# electrode_tester.net
KiCad netlist of a schematic drawn in EAGLE
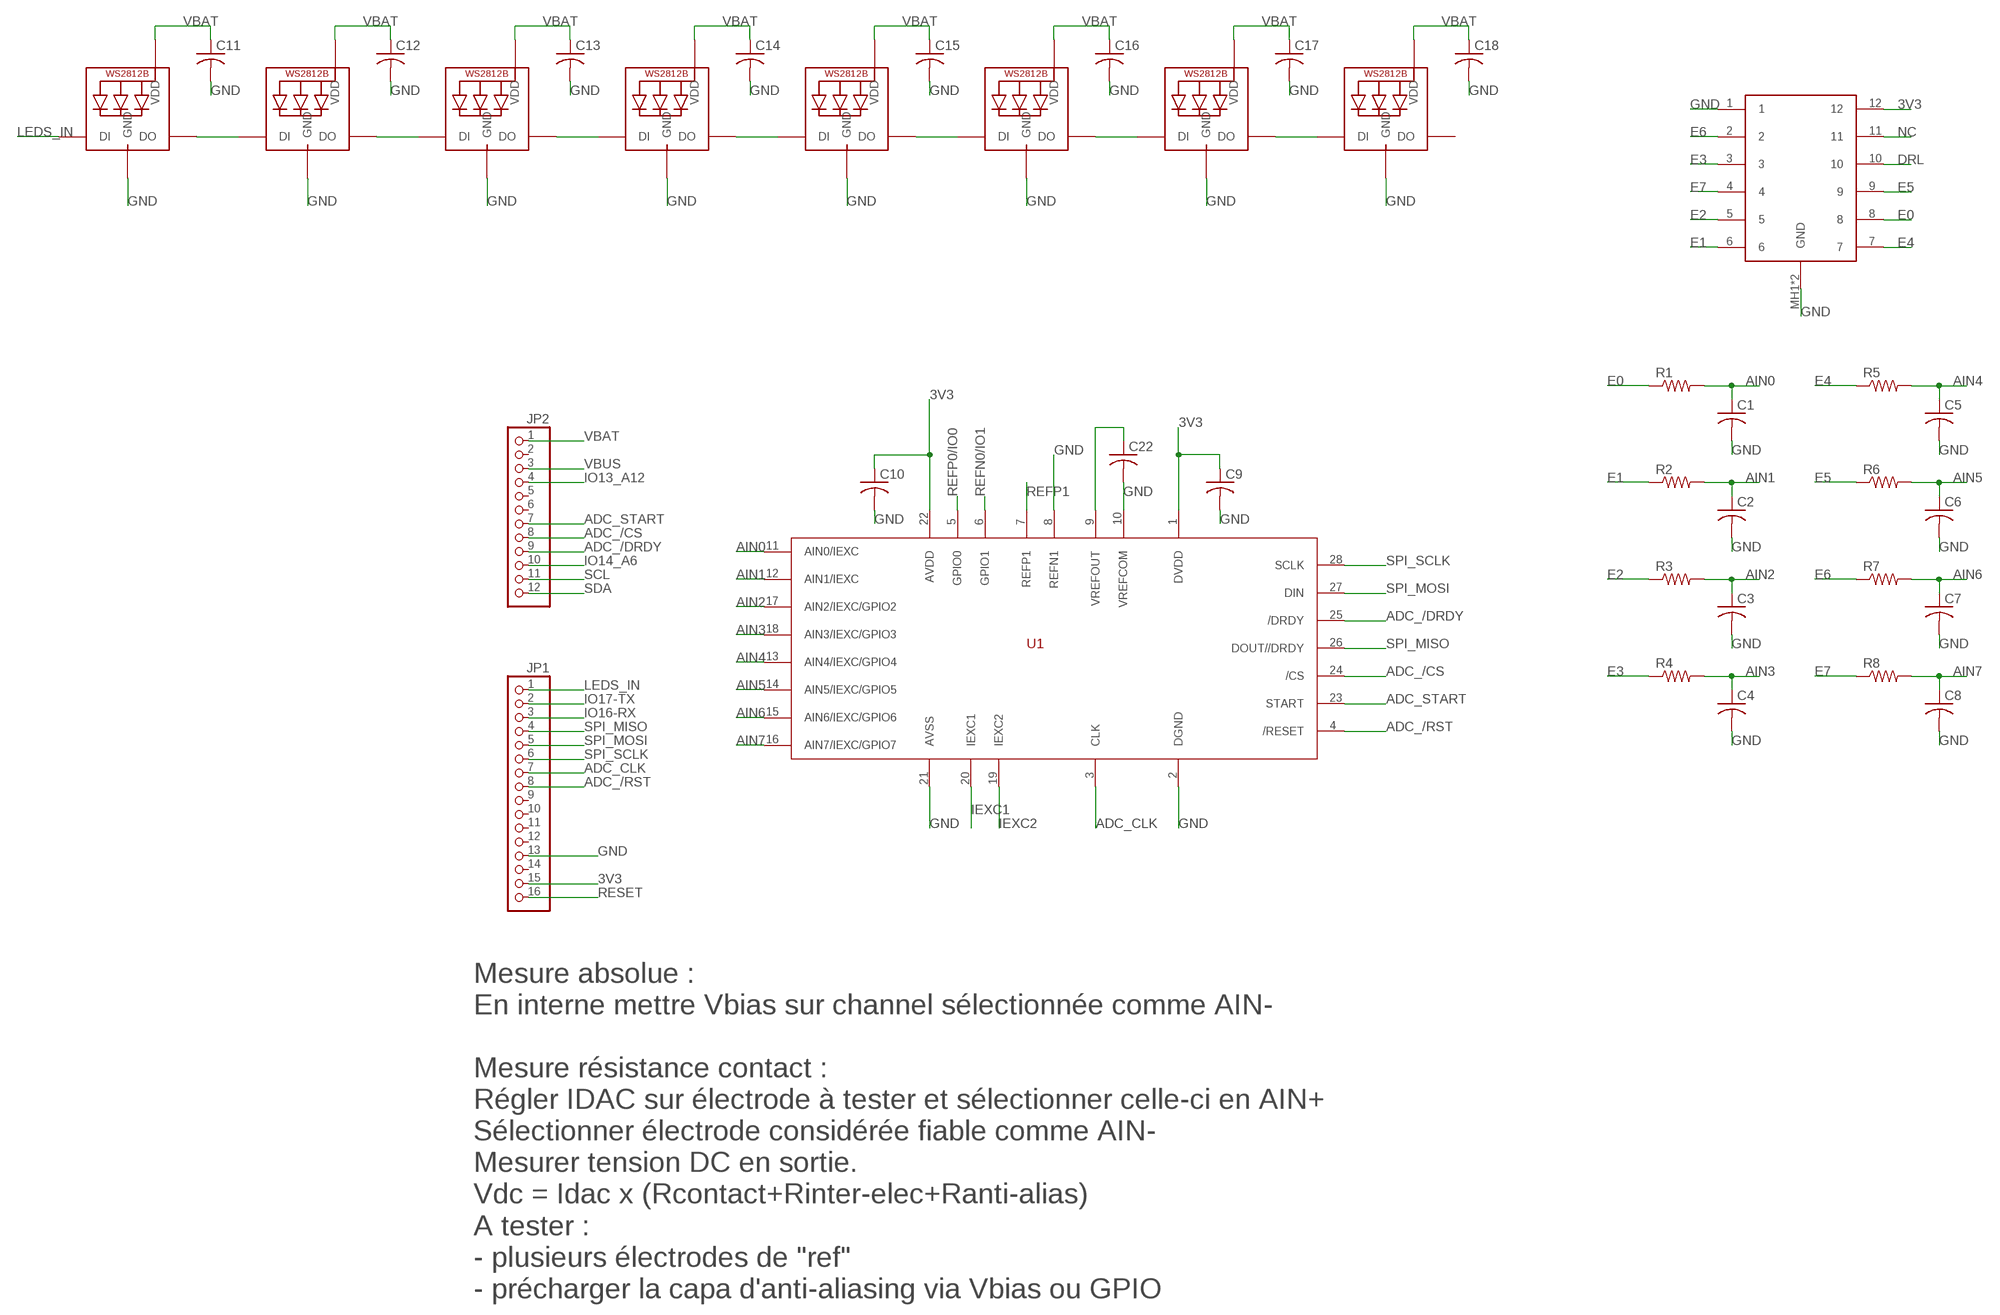
[diagram p0: schematic, sheet 1, part 1 of 2]
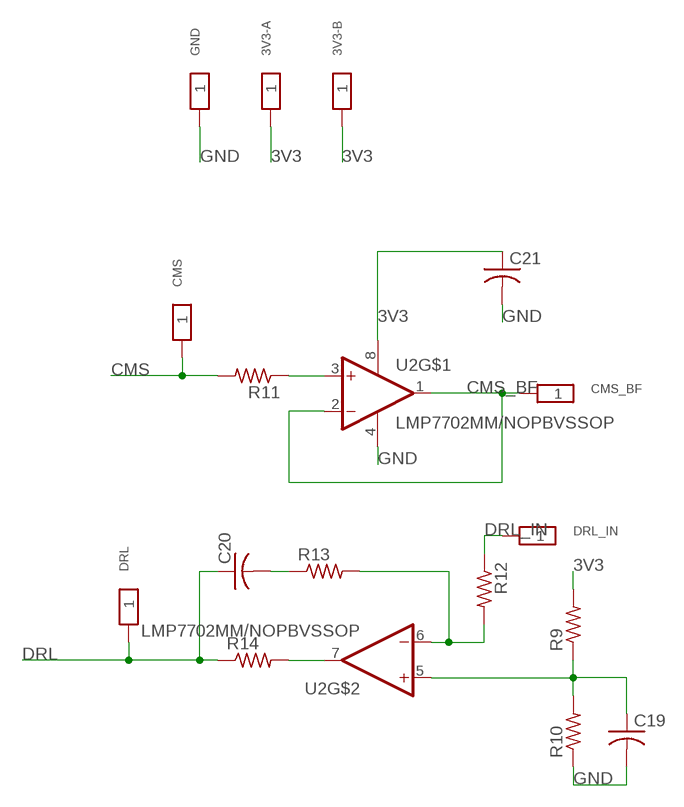
[diagram p1: schematic, sheet 1, part 2 of 2]

(export (version "E")
  (design (tool "Eeschema 10.0.6"))
  (components
    (comp (ref "3V3-A")
      (value "TESTPAD_PROG")
      (footprint "eagle-import:TP1.5MM")
      (libsource (lib "eagle-import") (part "TESTPAD_PROG"))
    )
    (comp (ref "3V3-B")
      (value "TESTPAD_PROG")
      (footprint "eagle-import:TP1.5MM")
      (libsource (lib "eagle-import") (part "TESTPAD_PROG"))
    )
    (comp (ref "C1")
      (value "C-USC0603")
      (footprint "eagle-import:C0603")
      (libsource (lib "eagle-import") (part "C-USC0603"))
    )
    (comp (ref "C2")
      (value "C-USC0603")
      (footprint "eagle-import:C0603")
      (libsource (lib "eagle-import") (part "C-USC0603"))
    )
    (comp (ref "C3")
      (value "C-USC0603")
      (footprint "eagle-import:C0603")
      (libsource (lib "eagle-import") (part "C-USC0603"))
    )
    (comp (ref "C4")
      (value "C-USC0603")
      (footprint "eagle-import:C0603")
      (libsource (lib "eagle-import") (part "C-USC0603"))
    )
    (comp (ref "C5")
      (value "C-USC0603")
      (footprint "eagle-import:C0603")
      (libsource (lib "eagle-import") (part "C-USC0603"))
    )
    (comp (ref "C6")
      (value "C-USC0603")
      (footprint "eagle-import:C0603")
      (libsource (lib "eagle-import") (part "C-USC0603"))
    )
    (comp (ref "C7")
      (value "C-USC0603")
      (footprint "eagle-import:C0603")
      (libsource (lib "eagle-import") (part "C-USC0603"))
    )
    (comp (ref "C8")
      (value "C-USC0603")
      (footprint "eagle-import:C0603")
      (libsource (lib "eagle-import") (part "C-USC0603"))
    )
    (comp (ref "C9")
      (value "C-USC0603")
      (footprint "eagle-import:C0603")
      (libsource (lib "eagle-import") (part "C-USC0603"))
    )
    (comp (ref "C10")
      (value "C-USC0603")
      (footprint "eagle-import:C0603")
      (libsource (lib "eagle-import") (part "C-USC0603"))
    )
    (comp (ref "C11")
      (value "C-USC0603")
      (footprint "eagle-import:C0603")
      (libsource (lib "eagle-import") (part "C-USC0603"))
    )
    (comp (ref "C12")
      (value "C-USC0603")
      (footprint "eagle-import:C0603")
      (libsource (lib "eagle-import") (part "C-USC0603"))
    )
    (comp (ref "C13")
      (value "C-USC0603")
      (footprint "eagle-import:C0603")
      (libsource (lib "eagle-import") (part "C-USC0603"))
    )
    (comp (ref "C14")
      (value "C-USC0603")
      (footprint "eagle-import:C0603")
      (libsource (lib "eagle-import") (part "C-USC0603"))
    )
    (comp (ref "C15")
      (value "C-USC0603")
      (footprint "eagle-import:C0603")
      (libsource (lib "eagle-import") (part "C-USC0603"))
    )
    (comp (ref "C16")
      (value "C-USC0603")
      (footprint "eagle-import:C0603")
      (libsource (lib "eagle-import") (part "C-USC0603"))
    )
    (comp (ref "C17")
      (value "C-USC0603")
      (footprint "eagle-import:C0603")
      (libsource (lib "eagle-import") (part "C-USC0603"))
    )
    (comp (ref "C18")
      (value "C-USC0603")
      (footprint "eagle-import:C0603")
      (libsource (lib "eagle-import") (part "C-USC0603"))
    )
    (comp (ref "C19")
      (value "C-USC0603")
      (footprint "eagle-import:C0603")
      (libsource (lib "eagle-import") (part "C-USC0603"))
    )
    (comp (ref "C20")
      (value "C-USC0603")
      (footprint "eagle-import:C0603")
      (libsource (lib "eagle-import") (part "C-USC0603"))
    )
    (comp (ref "C21")
      (value "C-USC0603")
      (footprint "eagle-import:C0603")
      (libsource (lib "eagle-import") (part "C-USC0603"))
    )
    (comp (ref "C22")
      (value "C-USC0603")
      (footprint "eagle-import:C0603")
      (libsource (lib "eagle-import") (part "C-USC0603"))
    )
    (comp (ref "CMS")
      (value "TESTPAD_PROG")
      (footprint "eagle-import:TP1.5MM")
      (libsource (lib "eagle-import") (part "TESTPAD_PROG"))
    )
    (comp (ref "CMS_BF")
      (value "TESTPAD_PROG")
      (footprint "eagle-import:TP1.5MM")
      (libsource (lib "eagle-import") (part "TESTPAD_PROG"))
    )
    (comp (ref "CONN1")
      (value "505110-1292")
      (footprint "eagle-import:505110-1292")
      (libsource (lib "eagle-import") (part "505110-1292"))
    )
    (comp (ref "DRL")
      (value "TESTPAD_PROG")
      (footprint "eagle-import:TP1.5MM")
      (libsource (lib "eagle-import") (part "TESTPAD_PROG"))
    )
    (comp (ref "DRL_IN")
      (value "TESTPAD_PROG")
      (footprint "eagle-import:TP1.5MM")
      (libsource (lib "eagle-import") (part "TESTPAD_PROG"))
    )
    (comp (ref "GND")
      (value "TESTPAD_PROG")
      (footprint "eagle-import:TP1.5MM")
      (libsource (lib "eagle-import") (part "TESTPAD_PROG"))
    )
    (comp (ref "JP1")
      (value "HEADER-1X16ROUND")
      (footprint "eagle-import:1X16_ROUND")
      (libsource (lib "eagle-import") (part "HEADER-1X16ROUND"))
    )
    (comp (ref "JP2")
      (value "HEADER-1X12")
      (footprint "eagle-import:1X12_ROUND")
      (libsource (lib "eagle-import") (part "HEADER-1X12"))
    )
    (comp (ref "LED1")
      (value "WS2812B5050")
      (footprint "eagle-import:WS2812B")
      (libsource (lib "eagle-import") (part "WS2812B5050"))
    )
    (comp (ref "LED2")
      (value "WS2812B5050")
      (footprint "eagle-import:WS2812B")
      (libsource (lib "eagle-import") (part "WS2812B5050"))
    )
    (comp (ref "LED3")
      (value "WS2812B5050")
      (footprint "eagle-import:WS2812B")
      (libsource (lib "eagle-import") (part "WS2812B5050"))
    )
    (comp (ref "LED4")
      (value "WS2812B5050")
      (footprint "eagle-import:WS2812B")
      (libsource (lib "eagle-import") (part "WS2812B5050"))
    )
    (comp (ref "LED5")
      (value "WS2812B5050")
      (footprint "eagle-import:WS2812B")
      (libsource (lib "eagle-import") (part "WS2812B5050"))
    )
    (comp (ref "LED6")
      (value "WS2812B5050")
      (footprint "eagle-import:WS2812B")
      (libsource (lib "eagle-import") (part "WS2812B5050"))
    )
    (comp (ref "LED7")
      (value "WS2812B5050")
      (footprint "eagle-import:WS2812B")
      (libsource (lib "eagle-import") (part "WS2812B5050"))
    )
    (comp (ref "LED8")
      (value "WS2812B5050")
      (footprint "eagle-import:WS2812B")
      (libsource (lib "eagle-import") (part "WS2812B5050"))
    )
    (comp (ref "R1")
      (value "R-US_R0603")
      (footprint "eagle-import:R0603")
      (libsource (lib "eagle-import") (part "R-US_R0603"))
    )
    (comp (ref "R2")
      (value "R-US_R0603")
      (footprint "eagle-import:R0603")
      (libsource (lib "eagle-import") (part "R-US_R0603"))
    )
    (comp (ref "R3")
      (value "R-US_R0603")
      (footprint "eagle-import:R0603")
      (libsource (lib "eagle-import") (part "R-US_R0603"))
    )
    (comp (ref "R4")
      (value "R-US_R0603")
      (footprint "eagle-import:R0603")
      (libsource (lib "eagle-import") (part "R-US_R0603"))
    )
    (comp (ref "R5")
      (value "R-US_R0603")
      (footprint "eagle-import:R0603")
      (libsource (lib "eagle-import") (part "R-US_R0603"))
    )
    (comp (ref "R6")
      (value "R-US_R0603")
      (footprint "eagle-import:R0603")
      (libsource (lib "eagle-import") (part "R-US_R0603"))
    )
    (comp (ref "R7")
      (value "R-US_R0603")
      (footprint "eagle-import:R0603")
      (libsource (lib "eagle-import") (part "R-US_R0603"))
    )
    (comp (ref "R8")
      (value "R-US_R0603")
      (footprint "eagle-import:R0603")
      (libsource (lib "eagle-import") (part "R-US_R0603"))
    )
    (comp (ref "R9")
      (value "R-US_R0603")
      (footprint "eagle-import:R0603")
      (libsource (lib "eagle-import") (part "R-US_R0603"))
    )
    (comp (ref "R10")
      (value "R-US_R0603")
      (footprint "eagle-import:R0603")
      (libsource (lib "eagle-import") (part "R-US_R0603"))
    )
    (comp (ref "R11")
      (value "R-US_R0603")
      (footprint "eagle-import:R0603")
      (libsource (lib "eagle-import") (part "R-US_R0603"))
    )
    (comp (ref "R12")
      (value "R-US_R0603")
      (footprint "eagle-import:R0603")
      (libsource (lib "eagle-import") (part "R-US_R0603"))
    )
    (comp (ref "R13")
      (value "R-US_R0603")
      (footprint "eagle-import:R0603")
      (libsource (lib "eagle-import") (part "R-US_R0603"))
    )
    (comp (ref "R14")
      (value "R-US_R0603")
      (footprint "eagle-import:R0603")
      (libsource (lib "eagle-import") (part "R-US_R0603"))
    )
    (comp (ref "U1")
      (value "ADS1248")
      (footprint "eagle-import:TSSOP28")
      (libsource (lib "eagle-import") (part "ADS1248"))
    )
    (comp (ref "U2")
      (value "LMP7702MM/NOPBVSSOP")
      (footprint "eagle-import:VSSOP8")
      (fields (field (name "MF") "Texas Instruments") (field (name "MP") "LMP7702MM/NOPB"))
      (libsource (lib "eagle-import") (part "LMP7702MM/NOPBVSSOP"))
    )
  )
  (nets
    (net (code "1") (name "/3V3") (class "Default")
      (node (ref "3V3-A") (pin "1") (pinfunction "1_1") (pintype "bidirectional"))
      (node (ref "3V3-B") (pin "1") (pinfunction "1_1") (pintype "bidirectional"))
      (node (ref "C10") (pin "1") (pinfunction "1_1") (pintype "passive"))
      (node (ref "C21") (pin "1") (pinfunction "1_1") (pintype "passive"))
      (node (ref "C9") (pin "1") (pinfunction "1_1") (pintype "passive"))
      (node (ref "CONN1") (pin "12") (pinfunction "12_12") (pintype "bidirectional"))
      (node (ref "JP1") (pin "15") (pinfunction "15_15") (pintype "passive"))
      (node (ref "R9") (pin "2") (pinfunction "2_2") (pintype "passive"))
      (node (ref "U1") (pin "1") (pinfunction "DVDD_1") (pintype "bidirectional"))
      (node (ref "U1") (pin "22") (pinfunction "AVDD_22") (pintype "bidirectional"))
      (node (ref "U2") (pin "8") (pinfunction "V+_8") (pintype "power_in"))
    )
    (net (code "2") (name "/ADC_CLK") (class "Default")
      (node (ref "JP1") (pin "7") (pinfunction "7_7") (pintype "passive"))
      (node (ref "U1") (pin "3") (pinfunction "CLK_3") (pintype "bidirectional"))
    )
    (net (code "3") (name "/ADC_START") (class "Default")
      (node (ref "JP2") (pin "7") (pinfunction "7_7") (pintype "passive"))
      (node (ref "U1") (pin "23") (pinfunction "START_23") (pintype "bidirectional"))
    )
    (net (code "4") (name "/ADC_{slash}CS") (class "Default")
      (node (ref "JP2") (pin "8") (pinfunction "8_8") (pintype "passive"))
      (node (ref "U1") (pin "24") (pinfunction "/CS_24") (pintype "bidirectional"))
    )
    (net (code "5") (name "/ADC_{slash}DRDY") (class "Default")
      (node (ref "JP2") (pin "9") (pinfunction "9_9") (pintype "passive"))
      (node (ref "U1") (pin "25") (pinfunction "/DRDY_25") (pintype "bidirectional"))
    )
    (net (code "6") (name "/ADC_{slash}RST") (class "Default")
      (node (ref "JP1") (pin "8") (pinfunction "8_8") (pintype "passive"))
      (node (ref "U1") (pin "4") (pinfunction "/RESET_4") (pintype "bidirectional"))
    )
    (net (code "7") (name "/AIN0") (class "Default")
      (node (ref "C1") (pin "1") (pinfunction "1_1") (pintype "passive"))
      (node (ref "R1") (pin "2") (pinfunction "2_2") (pintype "passive"))
      (node (ref "U1") (pin "11") (pinfunction "AIN0/IEXC_11") (pintype "bidirectional"))
    )
    (net (code "8") (name "/AIN1") (class "Default")
      (node (ref "C2") (pin "1") (pinfunction "1_1") (pintype "passive"))
      (node (ref "R2") (pin "2") (pinfunction "2_2") (pintype "passive"))
      (node (ref "U1") (pin "12") (pinfunction "AIN1/IEXC_12") (pintype "bidirectional"))
    )
    (net (code "9") (name "/AIN2") (class "Default")
      (node (ref "C3") (pin "1") (pinfunction "1_1") (pintype "passive"))
      (node (ref "R3") (pin "2") (pinfunction "2_2") (pintype "passive"))
      (node (ref "U1") (pin "17") (pinfunction "AIN2/IEXC/GPIO2_17") (pintype "bidirectional"))
    )
    (net (code "10") (name "/AIN3") (class "Default")
      (node (ref "C4") (pin "1") (pinfunction "1_1") (pintype "passive"))
      (node (ref "R4") (pin "2") (pinfunction "2_2") (pintype "passive"))
      (node (ref "U1") (pin "18") (pinfunction "AIN3/IEXC/GPIO3_18") (pintype "bidirectional"))
    )
    (net (code "11") (name "/AIN4") (class "Default")
      (node (ref "C5") (pin "1") (pinfunction "1_1") (pintype "passive"))
      (node (ref "R5") (pin "2") (pinfunction "2_2") (pintype "passive"))
      (node (ref "U1") (pin "13") (pinfunction "AIN4/IEXC/GPIO4_13") (pintype "bidirectional"))
    )
    (net (code "12") (name "/AIN5") (class "Default")
      (node (ref "C6") (pin "1") (pinfunction "1_1") (pintype "passive"))
      (node (ref "R6") (pin "2") (pinfunction "2_2") (pintype "passive"))
      (node (ref "U1") (pin "14") (pinfunction "AIN5/IEXC/GPIO5_14") (pintype "bidirectional"))
    )
    (net (code "13") (name "/AIN6") (class "Default")
      (node (ref "C7") (pin "1") (pinfunction "1_1") (pintype "passive"))
      (node (ref "R7") (pin "2") (pinfunction "2_2") (pintype "passive"))
      (node (ref "U1") (pin "15") (pinfunction "AIN6/IEXC/GPIO6_15") (pintype "bidirectional"))
    )
    (net (code "14") (name "/AIN7") (class "Default")
      (node (ref "C8") (pin "1") (pinfunction "1_1") (pintype "passive"))
      (node (ref "R8") (pin "2") (pinfunction "2_2") (pintype "passive"))
      (node (ref "U1") (pin "16") (pinfunction "AIN7/IEXC/GPIO7_16") (pintype "bidirectional"))
    )
    (net (code "15") (name "/CMS") (class "Default")
      (node (ref "CMS") (pin "1") (pinfunction "1_1") (pintype "bidirectional"))
      (node (ref "R11") (pin "2") (pinfunction "2_2") (pintype "passive"))
    )
    (net (code "16") (name "/CMS_BF") (class "Default")
      (node (ref "CMS_BF") (pin "1") (pinfunction "1_1") (pintype "bidirectional"))
      (node (ref "U2") (pin "1") (pinfunction "OUT_1") (pintype "output"))
      (node (ref "U2") (pin "2") (pinfunction "-IN_2") (pintype "input"))
    )
    (net (code "17") (name "/DRL") (class "Default")
      (node (ref "C20") (pin "1") (pinfunction "1_1") (pintype "passive"))
      (node (ref "CONN1") (pin "10") (pinfunction "10_10") (pintype "bidirectional"))
      (node (ref "DRL") (pin "1") (pinfunction "1_1") (pintype "bidirectional"))
      (node (ref "R14") (pin "1") (pinfunction "1_1") (pintype "passive"))
    )
    (net (code "18") (name "/DRL_IN") (class "Default")
      (node (ref "DRL_IN") (pin "1") (pinfunction "1_1") (pintype "bidirectional"))
      (node (ref "R12") (pin "1") (pinfunction "1_1") (pintype "passive"))
    )
    (net (code "19") (name "/E0") (class "Default")
      (node (ref "CONN1") (pin "8") (pinfunction "8_8") (pintype "bidirectional"))
      (node (ref "R1") (pin "1") (pinfunction "1_1") (pintype "passive"))
    )
    (net (code "20") (name "/E1") (class "Default")
      (node (ref "CONN1") (pin "6") (pinfunction "6_6") (pintype "bidirectional"))
      (node (ref "R2") (pin "1") (pinfunction "1_1") (pintype "passive"))
    )
    (net (code "21") (name "/E2") (class "Default")
      (node (ref "CONN1") (pin "5") (pinfunction "5_5") (pintype "bidirectional"))
      (node (ref "R3") (pin "1") (pinfunction "1_1") (pintype "passive"))
    )
    (net (code "22") (name "/E3") (class "Default")
      (node (ref "CONN1") (pin "3") (pinfunction "3_3") (pintype "bidirectional"))
      (node (ref "R4") (pin "1") (pinfunction "1_1") (pintype "passive"))
    )
    (net (code "23") (name "/E4") (class "Default")
      (node (ref "CONN1") (pin "7") (pinfunction "7_7") (pintype "bidirectional"))
      (node (ref "R5") (pin "1") (pinfunction "1_1") (pintype "passive"))
    )
    (net (code "24") (name "/E5") (class "Default")
      (node (ref "CONN1") (pin "9") (pinfunction "9_9") (pintype "bidirectional"))
      (node (ref "R6") (pin "1") (pinfunction "1_1") (pintype "passive"))
    )
    (net (code "25") (name "/E6") (class "Default")
      (node (ref "CONN1") (pin "2") (pinfunction "2_2") (pintype "bidirectional"))
      (node (ref "R7") (pin "1") (pinfunction "1_1") (pintype "passive"))
    )
    (net (code "26") (name "/E7") (class "Default")
      (node (ref "CONN1") (pin "4") (pinfunction "4_4") (pintype "bidirectional"))
      (node (ref "R8") (pin "1") (pinfunction "1_1") (pintype "passive"))
    )
    (net (code "27") (name "/GND") (class "Default")
      (node (ref "C1") (pin "2") (pinfunction "2_2") (pintype "passive"))
      (node (ref "C10") (pin "2") (pinfunction "2_2") (pintype "passive"))
      (node (ref "C11") (pin "2") (pinfunction "2_2") (pintype "passive"))
      (node (ref "C12") (pin "2") (pinfunction "2_2") (pintype "passive"))
      (node (ref "C13") (pin "2") (pinfunction "2_2") (pintype "passive"))
      (node (ref "C14") (pin "2") (pinfunction "2_2") (pintype "passive"))
      (node (ref "C15") (pin "2") (pinfunction "2_2") (pintype "passive"))
      (node (ref "C16") (pin "2") (pinfunction "2_2") (pintype "passive"))
      (node (ref "C17") (pin "2") (pinfunction "2_2") (pintype "passive"))
      (node (ref "C18") (pin "2") (pinfunction "2_2") (pintype "passive"))
      (node (ref "C19") (pin "2") (pinfunction "2_2") (pintype "passive"))
      (node (ref "C2") (pin "2") (pinfunction "2_2") (pintype "passive"))
      (node (ref "C21") (pin "2") (pinfunction "2_2") (pintype "passive"))
      (node (ref "C22") (pin "2") (pinfunction "2_2") (pintype "passive"))
      (node (ref "C3") (pin "2") (pinfunction "2_2") (pintype "passive"))
      (node (ref "C4") (pin "2") (pinfunction "2_2") (pintype "passive"))
      (node (ref "C5") (pin "2") (pinfunction "2_2") (pintype "passive"))
      (node (ref "C6") (pin "2") (pinfunction "2_2") (pintype "passive"))
      (node (ref "C7") (pin "2") (pinfunction "2_2") (pintype "passive"))
      (node (ref "C8") (pin "2") (pinfunction "2_2") (pintype "passive"))
      (node (ref "C9") (pin "2") (pinfunction "2_2") (pintype "passive"))
      (node (ref "CONN1") (pin "1") (pinfunction "1_1") (pintype "bidirectional"))
      (node (ref "CONN1") (pin "MH1") (pinfunction "GND_MH1") (pintype "bidirectional"))
      (node (ref "CONN1") (pin "MH2") (pinfunction "GND_MH2") (pintype "bidirectional"))
      (node (ref "GND") (pin "1") (pinfunction "1_1") (pintype "bidirectional"))
      (node (ref "JP1") (pin "13") (pinfunction "13_13") (pintype "passive"))
      (node (ref "LED1") (pin "3-GND") (pinfunction "GND_3-GND") (pintype "power_in"))
      (node (ref "LED2") (pin "3-GND") (pinfunction "GND_3-GND") (pintype "power_in"))
      (node (ref "LED3") (pin "3-GND") (pinfunction "GND_3-GND") (pintype "power_in"))
      (node (ref "LED4") (pin "3-GND") (pinfunction "GND_3-GND") (pintype "power_in"))
      (node (ref "LED5") (pin "3-GND") (pinfunction "GND_3-GND") (pintype "power_in"))
      (node (ref "LED6") (pin "3-GND") (pinfunction "GND_3-GND") (pintype "power_in"))
      (node (ref "LED7") (pin "3-GND") (pinfunction "GND_3-GND") (pintype "power_in"))
      (node (ref "LED8") (pin "3-GND") (pinfunction "GND_3-GND") (pintype "power_in"))
      (node (ref "R10") (pin "1") (pinfunction "1_1") (pintype "passive"))
      (node (ref "U1") (pin "10") (pinfunction "VREFCOM_10") (pintype "bidirectional"))
      (node (ref "U1") (pin "2") (pinfunction "DGND_2") (pintype "bidirectional"))
      (node (ref "U1") (pin "21") (pinfunction "AVSS_21") (pintype "bidirectional"))
      (node (ref "U1") (pin "8") (pinfunction "REFN1_8") (pintype "bidirectional"))
      (node (ref "U2") (pin "4") (pinfunction "V-_4") (pintype "power_in"))
    )
    (net (code "28") (name "/IEXC1") (class "Default")
      (node (ref "U1") (pin "20") (pinfunction "IEXC1_20") (pintype "bidirectional"))
    )
    (net (code "29") (name "/IEXC2") (class "Default")
      (node (ref "U1") (pin "19") (pinfunction "IEXC2_19") (pintype "bidirectional"))
    )
    (net (code "30") (name "/IO13_A12") (class "Default")
      (node (ref "JP2") (pin "4") (pinfunction "4_4") (pintype "passive"))
    )
    (net (code "31") (name "/IO14_A6") (class "Default")
      (node (ref "JP2") (pin "10") (pinfunction "10_10") (pintype "passive"))
    )
    (net (code "32") (name "/IO16-RX") (class "Default")
      (node (ref "JP1") (pin "3") (pinfunction "3_3") (pintype "passive"))
    )
    (net (code "33") (name "/IO17-TX") (class "Default")
      (node (ref "JP1") (pin "2") (pinfunction "2_2") (pintype "passive"))
    )
    (net (code "34") (name "/LEDS_IN") (class "Default")
      (node (ref "JP1") (pin "1") (pinfunction "1_1") (pintype "passive"))
      (node (ref "LED1") (pin "4-DIN") (pinfunction "DI_4-DIN") (pintype "input"))
    )
    (net (code "35") (name "/NC") (class "Default")
      (node (ref "CONN1") (pin "11") (pinfunction "11_11") (pintype "bidirectional"))
    )
    (net (code "36") (name "/REFN0{slash}IO1") (class "Default")
      (node (ref "U1") (pin "6") (pinfunction "GPIO1_6") (pintype "bidirectional"))
    )
    (net (code "37") (name "/REFP0{slash}IO0") (class "Default")
      (node (ref "U1") (pin "5") (pinfunction "GPIO0_5") (pintype "bidirectional"))
    )
    (net (code "38") (name "/REFP1") (class "Default")
      (node (ref "U1") (pin "7") (pinfunction "REFP1_7") (pintype "bidirectional"))
    )
    (net (code "39") (name "/RESET") (class "Default")
      (node (ref "JP1") (pin "16") (pinfunction "16_16") (pintype "passive"))
    )
    (net (code "40") (name "/SCL") (class "Default")
      (node (ref "JP2") (pin "11") (pinfunction "11_11") (pintype "passive"))
    )
    (net (code "41") (name "/SDA") (class "Default")
      (node (ref "JP2") (pin "12") (pinfunction "12_12") (pintype "passive"))
    )
    (net (code "42") (name "/SPI_MISO") (class "Default")
      (node (ref "JP1") (pin "4") (pinfunction "4_4") (pintype "passive"))
      (node (ref "U1") (pin "26") (pinfunction "DOUT//DRDY_26") (pintype "bidirectional"))
    )
    (net (code "43") (name "/SPI_MOSI") (class "Default")
      (node (ref "JP1") (pin "5") (pinfunction "5_5") (pintype "passive"))
      (node (ref "U1") (pin "27") (pinfunction "DIN_27") (pintype "bidirectional"))
    )
    (net (code "44") (name "/SPI_SCLK") (class "Default")
      (node (ref "JP1") (pin "6") (pinfunction "6_6") (pintype "passive"))
      (node (ref "U1") (pin "28") (pinfunction "SCLK_28") (pintype "bidirectional"))
    )
    (net (code "45") (name "/VBAT") (class "Default")
      (node (ref "C11") (pin "1") (pinfunction "1_1") (pintype "passive"))
      (node (ref "C12") (pin "1") (pinfunction "1_1") (pintype "passive"))
      (node (ref "C13") (pin "1") (pinfunction "1_1") (pintype "passive"))
      (node (ref "C14") (pin "1") (pinfunction "1_1") (pintype "passive"))
      (node (ref "C15") (pin "1") (pinfunction "1_1") (pintype "passive"))
      (node (ref "C16") (pin "1") (pinfunction "1_1") (pintype "passive"))
      (node (ref "C17") (pin "1") (pinfunction "1_1") (pintype "passive"))
      (node (ref "C18") (pin "1") (pinfunction "1_1") (pintype "passive"))
      (node (ref "JP2") (pin "1") (pinfunction "1_1") (pintype "passive"))
      (node (ref "LED1") (pin "1-VDD") (pinfunction "VDD_1-VDD") (pintype "power_in"))
      (node (ref "LED2") (pin "1-VDD") (pinfunction "VDD_1-VDD") (pintype "power_in"))
      (node (ref "LED3") (pin "1-VDD") (pinfunction "VDD_1-VDD") (pintype "power_in"))
      (node (ref "LED4") (pin "1-VDD") (pinfunction "VDD_1-VDD") (pintype "power_in"))
      (node (ref "LED5") (pin "1-VDD") (pinfunction "VDD_1-VDD") (pintype "power_in"))
      (node (ref "LED6") (pin "1-VDD") (pinfunction "VDD_1-VDD") (pintype "power_in"))
      (node (ref "LED7") (pin "1-VDD") (pinfunction "VDD_1-VDD") (pintype "power_in"))
      (node (ref "LED8") (pin "1-VDD") (pinfunction "VDD_1-VDD") (pintype "power_in"))
    )
    (net (code "46") (name "/VBUS") (class "Default")
      (node (ref "JP2") (pin "3") (pinfunction "3_3") (pintype "passive"))
    )
    (net (code "47") (name "Net-(C20-Pad2)") (class "Default")
      (node (ref "C20") (pin "2") (pinfunction "2_2") (pintype "passive"))
      (node (ref "R13") (pin "1") (pinfunction "1_1") (pintype "passive"))
    )
    (net (code "48") (name "Net-(LED1-DO)") (class "Default")
      (node (ref "LED1") (pin "2-DOUT") (pinfunction "DO_2-DOUT") (pintype "output"))
      (node (ref "LED2") (pin "4-DIN") (pinfunction "DI_4-DIN") (pintype "input"))
    )
    (net (code "49") (name "Net-(LED2-DO)") (class "Default")
      (node (ref "LED2") (pin "2-DOUT") (pinfunction "DO_2-DOUT") (pintype "output"))
      (node (ref "LED3") (pin "4-DIN") (pinfunction "DI_4-DIN") (pintype "input"))
    )
    (net (code "50") (name "Net-(LED3-DO)") (class "Default")
      (node (ref "LED3") (pin "2-DOUT") (pinfunction "DO_2-DOUT") (pintype "output"))
      (node (ref "LED4") (pin "4-DIN") (pinfunction "DI_4-DIN") (pintype "input"))
    )
    (net (code "51") (name "Net-(LED4-DO)") (class "Default")
      (node (ref "LED4") (pin "2-DOUT") (pinfunction "DO_2-DOUT") (pintype "output"))
      (node (ref "LED5") (pin "4-DIN") (pinfunction "DI_4-DIN") (pintype "input"))
    )
    (net (code "52") (name "Net-(LED5-DO)") (class "Default")
      (node (ref "LED5") (pin "2-DOUT") (pinfunction "DO_2-DOUT") (pintype "output"))
      (node (ref "LED6") (pin "4-DIN") (pinfunction "DI_4-DIN") (pintype "input"))
    )
    (net (code "53") (name "Net-(LED6-DO)") (class "Default")
      (node (ref "LED6") (pin "2-DOUT") (pinfunction "DO_2-DOUT") (pintype "output"))
      (node (ref "LED7") (pin "4-DIN") (pinfunction "DI_4-DIN") (pintype "input"))
    )
    (net (code "54") (name "Net-(LED7-DO)") (class "Default")
      (node (ref "LED7") (pin "2-DOUT") (pinfunction "DO_2-DOUT") (pintype "output"))
      (node (ref "LED8") (pin "4-DIN") (pinfunction "DI_4-DIN") (pintype "input"))
    )
    (net (code "55") (name "Net-(U1-VREFOUT)") (class "Default")
      (node (ref "C22") (pin "1") (pinfunction "1_1") (pintype "passive"))
      (node (ref "U1") (pin "9") (pinfunction "VREFOUT_9") (pintype "bidirectional"))
    )
    (net (code "56") (name "Net-(U2A-+IN)") (class "Default")
      (node (ref "R11") (pin "1") (pinfunction "1_1") (pintype "passive"))
      (node (ref "U2") (pin "3") (pinfunction "+IN_3") (pintype "input"))
    )
    (net (code "57") (name "Net-(U2B-+IN)") (class "Default")
      (node (ref "C19") (pin "1") (pinfunction "1_1") (pintype "passive"))
      (node (ref "R10") (pin "2") (pinfunction "2_2") (pintype "passive"))
      (node (ref "R9") (pin "1") (pinfunction "1_1") (pintype "passive"))
      (node (ref "U2") (pin "5") (pinfunction "+IN_5") (pintype "input"))
    )
    (net (code "58") (name "Net-(U2B--IN)") (class "Default")
      (node (ref "R12") (pin "2") (pinfunction "2_2") (pintype "passive"))
      (node (ref "R13") (pin "2") (pinfunction "2_2") (pintype "passive"))
      (node (ref "U2") (pin "6") (pinfunction "-IN_6") (pintype "input"))
    )
    (net (code "59") (name "Net-(U2B-OUT)") (class "Default")
      (node (ref "R14") (pin "2") (pinfunction "2_2") (pintype "passive"))
      (node (ref "U2") (pin "7") (pinfunction "OUT_7") (pintype "output"))
    )
    (net (code "60") (name "unconnected-(JP1-Pad9)") (class "Default")
      (node (ref "JP1") (pin "9") (pinfunction "9_9") (pintype "passive"))
    )
    (net (code "61") (name "unconnected-(JP1-Pad10)") (class "Default")
      (node (ref "JP1") (pin "10") (pinfunction "10_10") (pintype "passive"))
    )
    (net (code "62") (name "unconnected-(JP1-Pad11)") (class "Default")
      (node (ref "JP1") (pin "11") (pinfunction "11_11") (pintype "passive"))
    )
    (net (code "63") (name "unconnected-(JP1-Pad12)") (class "Default")
      (node (ref "JP1") (pin "12") (pinfunction "12_12") (pintype "passive"))
    )
    (net (code "64") (name "unconnected-(JP1-Pad14)") (class "Default")
      (node (ref "JP1") (pin "14") (pinfunction "14_14") (pintype "passive"))
    )
    (net (code "65") (name "unconnected-(JP2-Pad2)") (class "Default")
      (node (ref "JP2") (pin "2") (pinfunction "2_2") (pintype "passive"))
    )
    (net (code "66") (name "unconnected-(JP2-Pad5)") (class "Default")
      (node (ref "JP2") (pin "5") (pinfunction "5_5") (pintype "passive"))
    )
    (net (code "67") (name "unconnected-(JP2-Pad6)") (class "Default")
      (node (ref "JP2") (pin "6") (pinfunction "6_6") (pintype "passive"))
    )
    (net (code "68") (name "unconnected-(LED8-DO-Pad2-DOUT)") (class "Default")
      (node (ref "LED8") (pin "2-DOUT") (pinfunction "DO_2-DOUT") (pintype "output"))
    )
  )
)
